# ai_breakout_spi.net
KiCad netlist of a schematic drawn in EAGLE
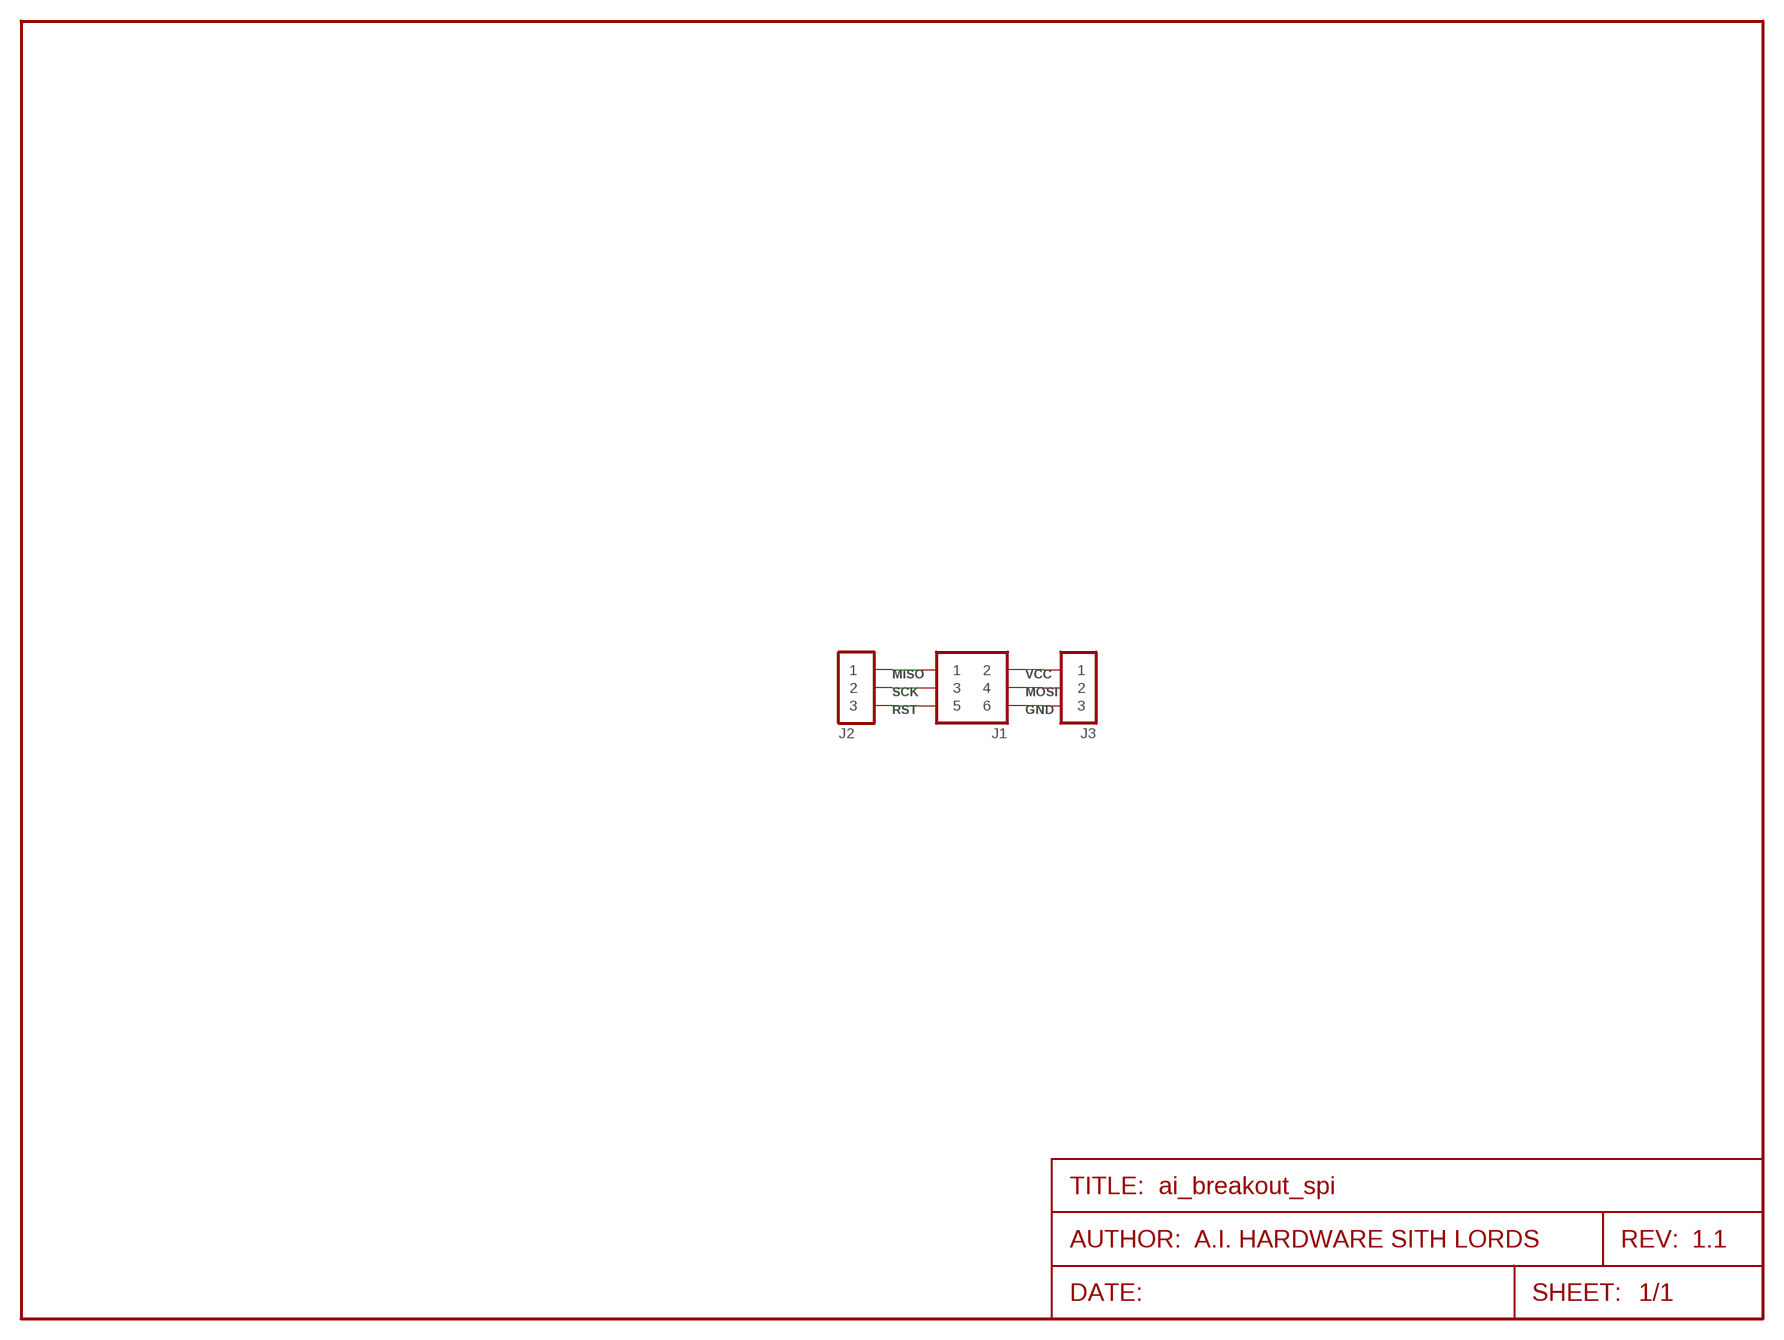
[diagram p0: schematic, sheet 1]

(export (version "E")
  (design (tool "Eeschema 10.0.6"))
  (components
    (comp (ref "J1")
      (value "2X03")
      (footprint "eagle-import:2X03")
      (libsource (lib "eagle-import") (part "2X03"))
    )
    (comp (ref "J2")
      (value "1X03")
      (footprint "eagle-import:1X03")
      (libsource (lib "eagle-import") (part "1X03"))
    )
    (comp (ref "J3")
      (value "1X03NOFIRST")
      (footprint "eagle-import:1X03-NOFIRST")
      (libsource (lib "eagle-import") (part "1X03NOFIRST"))
    )
  )
  (nets
    (net (code "1") (name "/GND") (class "Default")
      (node (ref "J1") (pin "6") (pinfunction "6_6") (pintype "bidirectional"))
      (node (ref "J3") (pin "3") (pinfunction "3_3") (pintype "bidirectional"))
    )
    (net (code "2") (name "/MISO") (class "Default")
      (node (ref "J1") (pin "1") (pinfunction "1_1") (pintype "bidirectional"))
      (node (ref "J2") (pin "1") (pinfunction "1_1") (pintype "bidirectional"))
    )
    (net (code "3") (name "/MOSI") (class "Default")
      (node (ref "J1") (pin "4") (pinfunction "4_4") (pintype "bidirectional"))
      (node (ref "J3") (pin "2") (pinfunction "2_2") (pintype "bidirectional"))
    )
    (net (code "4") (name "/RST") (class "Default")
      (node (ref "J1") (pin "5") (pinfunction "5_5") (pintype "bidirectional"))
      (node (ref "J2") (pin "3") (pinfunction "3_3") (pintype "bidirectional"))
    )
    (net (code "5") (name "/SCK") (class "Default")
      (node (ref "J1") (pin "3") (pinfunction "3_3") (pintype "bidirectional"))
      (node (ref "J2") (pin "2") (pinfunction "2_2") (pintype "bidirectional"))
    )
    (net (code "6") (name "/VCC") (class "Default")
      (node (ref "J1") (pin "2") (pinfunction "2_2") (pintype "bidirectional"))
      (node (ref "J3") (pin "1") (pinfunction "1_1") (pintype "bidirectional"))
    )
  )
)
